# comma_access_point.net
KiCad netlist of a schematic drawn in EAGLE
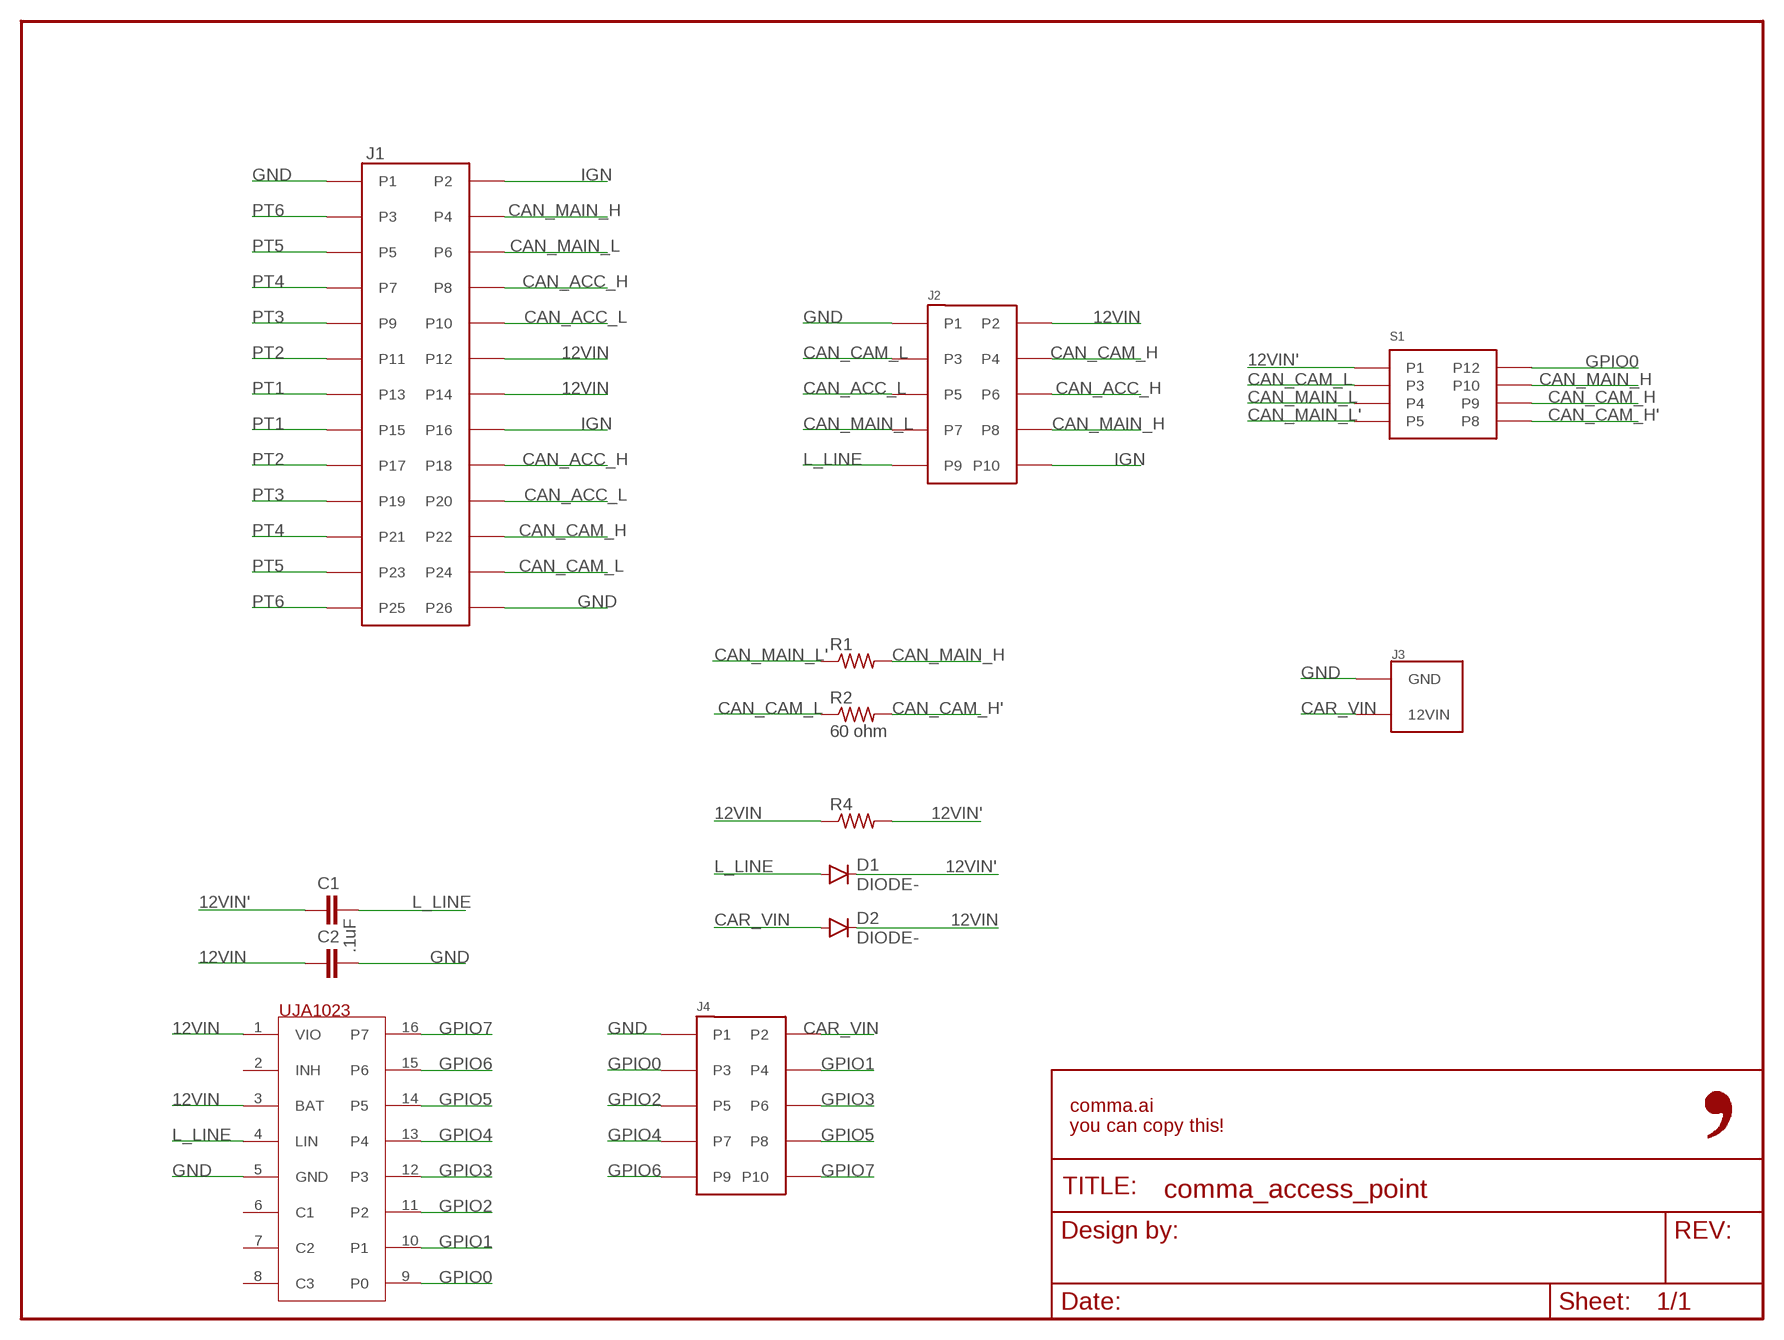
[diagram p0: schematic, sheet 1]

(export (version "E")
  (design (tool "Eeschema 10.0.6"))
  (components
    (comp (ref "C1")
      (value "C0805")
      (footprint "eagle-import:0805-C")
      (libsource (lib "eagle-import") (part "C0805"))
    )
    (comp (ref "C2")
      (value ".1uF")
      (footprint "eagle-import:0805-C")
      (libsource (lib "eagle-import") (part "C0805"))
    )
    (comp (ref "D1")
      (value "DIODE-")
      (footprint "eagle-import:DO-214")
      (libsource (lib "eagle-import") (part "DIODE-"))
    )
    (comp (ref "D2")
      (value "DIODE-")
      (footprint "eagle-import:DO-214")
      (libsource (lib "eagle-import") (part "DIODE-"))
    )
    (comp (ref "FRAME1")
      (value "FRAME-LETTER-OPENNO_PACKAGE")
      (footprint "eagle-import:DUMMY")
      (fields (field (name "DESIGNER") "Nobody"))
      (libsource (lib "eagle-import") (part "FRAME-LETTER-OPENNO_PACKAGE"))
    )
    (comp (ref "IC1")
      (value "UJA1023")
      (footprint "eagle-import:SO16")
      (libsource (lib "eagle-import") (part "UJA1023"))
    )
    (comp (ref "J1")
      (value "5018762640")
      (footprint "eagle-import:5018762640")
      (libsource (lib "eagle-import") (part "5018762640"))
    )
    (comp (ref "J2")
      (value "5018761040")
      (footprint "eagle-import:5018761040")
      (libsource (lib "eagle-import") (part "5018761040"))
    )
    (comp (ref "J3")
      (value "3-794618-2")
      (footprint "eagle-import:3-794618-2")
      (libsource (lib "eagle-import") (part "3-794618-2"))
    )
    (comp (ref "J4")
      (value "5018761040")
      (footprint "eagle-import:5018761040")
      (libsource (lib "eagle-import") (part "5018761040"))
    )
    (comp (ref "R1")
      (value "R0402")
      (footprint "eagle-import:0402-R")
      (libsource (lib "eagle-import") (part "R0402"))
    )
    (comp (ref "R2")
      (value "60 ohm")
      (footprint "eagle-import:0402-R")
      (libsource (lib "eagle-import") (part "R0402"))
    )
    (comp (ref "R4")
      (value "R0402")
      (footprint "eagle-import:0402-R")
      (libsource (lib "eagle-import") (part "R0402"))
    )
    (comp (ref "S1")
      (value "G6S-2G-DC12")
      (footprint "eagle-import:G6S-26-DC12")
      (libsource (lib "eagle-import") (part "G6S-2G-DC12"))
    )
  )
  (nets
    (net (code "1") (name "/12VIN") (class "Default")
      (node (ref "C2") (pin "1") (pinfunction "1_1") (pintype "passive"))
      (node (ref "D2") (pin "1") (pinfunction "C_1") (pintype "passive"))
      (node (ref "IC1") (pin "1") (pinfunction "VIO_1") (pintype "bidirectional"))
      (node (ref "IC1") (pin "3") (pinfunction "BAT_3") (pintype "bidirectional"))
      (node (ref "J1") (pin "P12") (pinfunction "P12_P12") (pintype "bidirectional"))
      (node (ref "J1") (pin "P14") (pinfunction "P14_P14") (pintype "bidirectional"))
      (node (ref "J2") (pin "P2") (pinfunction "P2_P2") (pintype "bidirectional"))
      (node (ref "R4") (pin "1") (pinfunction "1_1") (pintype "passive"))
    )
    (net (code "2") (name "/12VIN'") (class "Default")
      (node (ref "C1") (pin "1") (pinfunction "1_1") (pintype "passive"))
      (node (ref "D1") (pin "1") (pinfunction "C_1") (pintype "passive"))
      (node (ref "R4") (pin "2") (pinfunction "2_2") (pintype "passive"))
      (node (ref "S1") (pin "P1") (pinfunction "P1_P1") (pintype "bidirectional"))
    )
    (net (code "3") (name "/CAN_ACC_H") (class "Default")
      (node (ref "J1") (pin "P18") (pinfunction "P18_P18") (pintype "bidirectional"))
      (node (ref "J1") (pin "P8") (pinfunction "P8_P8") (pintype "bidirectional"))
      (node (ref "J2") (pin "P6") (pinfunction "P6_P6") (pintype "bidirectional"))
    )
    (net (code "4") (name "/CAN_ACC_L") (class "Default")
      (node (ref "J1") (pin "P10") (pinfunction "P10_P10") (pintype "bidirectional"))
      (node (ref "J1") (pin "P20") (pinfunction "P20_P20") (pintype "bidirectional"))
      (node (ref "J2") (pin "P5") (pinfunction "P5_P5") (pintype "bidirectional"))
    )
    (net (code "5") (name "/CAN_CAM_H") (class "Default")
      (node (ref "J1") (pin "P22") (pinfunction "P22_P22") (pintype "bidirectional"))
      (node (ref "J2") (pin "P4") (pinfunction "P4_P4") (pintype "bidirectional"))
      (node (ref "S1") (pin "P9") (pinfunction "P9_P9") (pintype "bidirectional"))
    )
    (net (code "6") (name "/CAN_CAM_H'") (class "Default")
      (node (ref "R2") (pin "2") (pinfunction "2_2") (pintype "passive"))
      (node (ref "S1") (pin "P8") (pinfunction "P8_P8") (pintype "bidirectional"))
    )
    (net (code "7") (name "/CAN_CAM_L") (class "Default")
      (node (ref "J1") (pin "P24") (pinfunction "P24_P24") (pintype "bidirectional"))
      (node (ref "J2") (pin "P3") (pinfunction "P3_P3") (pintype "bidirectional"))
      (node (ref "R2") (pin "1") (pinfunction "1_1") (pintype "passive"))
      (node (ref "S1") (pin "P3") (pinfunction "P3_P3") (pintype "bidirectional"))
    )
    (net (code "8") (name "/CAN_MAIN_H") (class "Default")
      (node (ref "J1") (pin "P4") (pinfunction "P4_P4") (pintype "bidirectional"))
      (node (ref "J2") (pin "P8") (pinfunction "P8_P8") (pintype "bidirectional"))
      (node (ref "R1") (pin "2") (pinfunction "2_2") (pintype "passive"))
      (node (ref "S1") (pin "P10") (pinfunction "P10_P10") (pintype "bidirectional"))
    )
    (net (code "9") (name "/CAN_MAIN_L") (class "Default")
      (node (ref "J1") (pin "P6") (pinfunction "P6_P6") (pintype "bidirectional"))
      (node (ref "J2") (pin "P7") (pinfunction "P7_P7") (pintype "bidirectional"))
      (node (ref "S1") (pin "P4") (pinfunction "P4_P4") (pintype "bidirectional"))
    )
    (net (code "10") (name "/CAN_MAIN_L'") (class "Default")
      (node (ref "R1") (pin "1") (pinfunction "1_1") (pintype "passive"))
      (node (ref "S1") (pin "P5") (pinfunction "P5_P5") (pintype "bidirectional"))
    )
    (net (code "11") (name "/CAR_VIN") (class "Default")
      (node (ref "D2") (pin "2") (pinfunction "A_2") (pintype "passive"))
      (node (ref "J3") (pin "12VIN") (pinfunction "12VIN_12VIN") (pintype "bidirectional"))
      (node (ref "J4") (pin "P2") (pinfunction "P2_P2") (pintype "bidirectional"))
    )
    (net (code "12") (name "/GND") (class "Default")
      (node (ref "C2") (pin "2") (pinfunction "2_2") (pintype "passive"))
      (node (ref "IC1") (pin "5") (pinfunction "GND_5") (pintype "bidirectional"))
      (node (ref "J1") (pin "P1") (pinfunction "P1_P1") (pintype "bidirectional"))
      (node (ref "J1") (pin "P26") (pinfunction "P26_P26") (pintype "bidirectional"))
      (node (ref "J2") (pin "P1") (pinfunction "P1_P1") (pintype "bidirectional"))
      (node (ref "J3") (pin "GND") (pinfunction "GND_GND") (pintype "bidirectional"))
      (node (ref "J4") (pin "P1") (pinfunction "P1_P1") (pintype "bidirectional"))
    )
    (net (code "13") (name "/GPIO0") (class "Default")
      (node (ref "IC1") (pin "9") (pinfunction "P0_9") (pintype "bidirectional"))
      (node (ref "J4") (pin "P3") (pinfunction "P3_P3") (pintype "bidirectional"))
      (node (ref "S1") (pin "P12") (pinfunction "P12_P12") (pintype "bidirectional"))
    )
    (net (code "14") (name "/GPIO1") (class "Default")
      (node (ref "IC1") (pin "10") (pinfunction "P1_10") (pintype "bidirectional"))
      (node (ref "J4") (pin "P4") (pinfunction "P4_P4") (pintype "bidirectional"))
    )
    (net (code "15") (name "/GPIO2") (class "Default")
      (node (ref "IC1") (pin "11") (pinfunction "P2_11") (pintype "bidirectional"))
      (node (ref "J4") (pin "P5") (pinfunction "P5_P5") (pintype "bidirectional"))
    )
    (net (code "16") (name "/GPIO3") (class "Default")
      (node (ref "IC1") (pin "12") (pinfunction "P3_12") (pintype "bidirectional"))
      (node (ref "J4") (pin "P6") (pinfunction "P6_P6") (pintype "bidirectional"))
    )
    (net (code "17") (name "/GPIO4") (class "Default")
      (node (ref "IC1") (pin "13") (pinfunction "P4_13") (pintype "bidirectional"))
      (node (ref "J4") (pin "P7") (pinfunction "P7_P7") (pintype "bidirectional"))
    )
    (net (code "18") (name "/GPIO5") (class "Default")
      (node (ref "IC1") (pin "14") (pinfunction "P5_14") (pintype "bidirectional"))
      (node (ref "J4") (pin "P8") (pinfunction "P8_P8") (pintype "bidirectional"))
    )
    (net (code "19") (name "/GPIO6") (class "Default")
      (node (ref "IC1") (pin "15") (pinfunction "P6_15") (pintype "bidirectional"))
      (node (ref "J4") (pin "P9") (pinfunction "P9_P9") (pintype "bidirectional"))
    )
    (net (code "20") (name "/GPIO7") (class "Default")
      (node (ref "IC1") (pin "16") (pinfunction "P7_16") (pintype "bidirectional"))
      (node (ref "J4") (pin "P10") (pinfunction "P10_P10") (pintype "bidirectional"))
    )
    (net (code "21") (name "/IGN") (class "Default")
      (node (ref "J1") (pin "P16") (pinfunction "P16_P16") (pintype "bidirectional"))
      (node (ref "J1") (pin "P2") (pinfunction "P2_P2") (pintype "bidirectional"))
      (node (ref "J2") (pin "P10") (pinfunction "P10_P10") (pintype "bidirectional"))
    )
    (net (code "22") (name "/L_LINE") (class "Default")
      (node (ref "C1") (pin "2") (pinfunction "2_2") (pintype "passive"))
      (node (ref "D1") (pin "2") (pinfunction "A_2") (pintype "passive"))
      (node (ref "IC1") (pin "4") (pinfunction "LIN_4") (pintype "bidirectional"))
      (node (ref "J2") (pin "P9") (pinfunction "P9_P9") (pintype "bidirectional"))
    )
    (net (code "23") (name "/PT1") (class "Default")
      (node (ref "J1") (pin "P13") (pinfunction "P13_P13") (pintype "bidirectional"))
      (node (ref "J1") (pin "P15") (pinfunction "P15_P15") (pintype "bidirectional"))
    )
    (net (code "24") (name "/PT2") (class "Default")
      (node (ref "J1") (pin "P11") (pinfunction "P11_P11") (pintype "bidirectional"))
      (node (ref "J1") (pin "P17") (pinfunction "P17_P17") (pintype "bidirectional"))
    )
    (net (code "25") (name "/PT3") (class "Default")
      (node (ref "J1") (pin "P19") (pinfunction "P19_P19") (pintype "bidirectional"))
      (node (ref "J1") (pin "P9") (pinfunction "P9_P9") (pintype "bidirectional"))
    )
    (net (code "26") (name "/PT4") (class "Default")
      (node (ref "J1") (pin "P21") (pinfunction "P21_P21") (pintype "bidirectional"))
      (node (ref "J1") (pin "P7") (pinfunction "P7_P7") (pintype "bidirectional"))
    )
    (net (code "27") (name "/PT5") (class "Default")
      (node (ref "J1") (pin "P23") (pinfunction "P23_P23") (pintype "bidirectional"))
      (node (ref "J1") (pin "P5") (pinfunction "P5_P5") (pintype "bidirectional"))
    )
    (net (code "28") (name "/PT6") (class "Default")
      (node (ref "J1") (pin "P25") (pinfunction "P25_P25") (pintype "bidirectional"))
      (node (ref "J1") (pin "P3") (pinfunction "P3_P3") (pintype "bidirectional"))
    )
    (net (code "29") (name "unconnected-(IC1-C1-Pad6)") (class "Default")
      (node (ref "IC1") (pin "6") (pinfunction "C1_6") (pintype "bidirectional"))
    )
    (net (code "30") (name "unconnected-(IC1-C2-Pad7)") (class "Default")
      (node (ref "IC1") (pin "7") (pinfunction "C2_7") (pintype "bidirectional"))
    )
    (net (code "31") (name "unconnected-(IC1-C3-Pad8)") (class "Default")
      (node (ref "IC1") (pin "8") (pinfunction "C3_8") (pintype "bidirectional"))
    )
    (net (code "32") (name "unconnected-(IC1-INH-Pad2)") (class "Default")
      (node (ref "IC1") (pin "2") (pinfunction "INH_2") (pintype "bidirectional"))
    )
  )
)
